# DROduino_v1.net
KiCad netlist of a schematic drawn in EAGLE
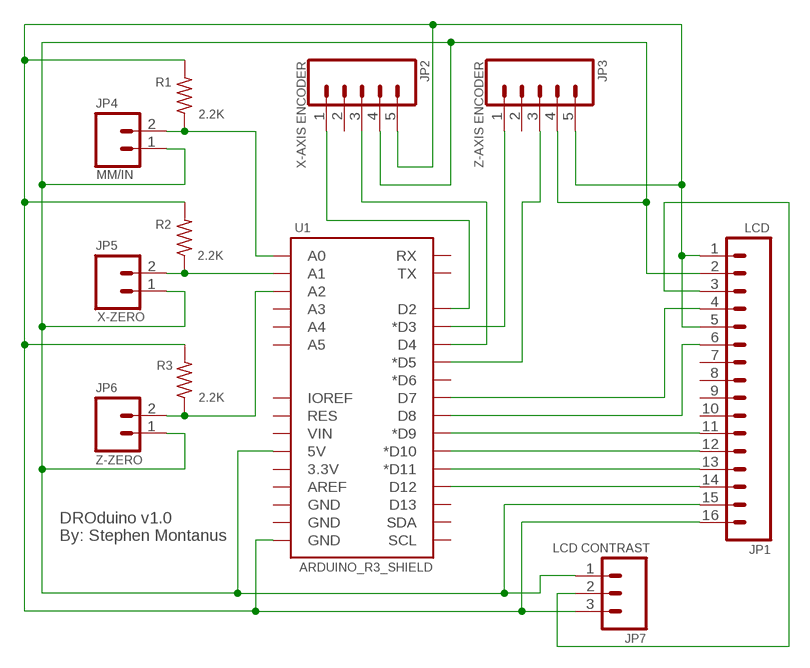
[diagram p0: schematic, sheet 1]

(export (version "E")
  (design (tool "Eeschema 10.0.6"))
  (components
    (comp (ref "JP1")
      (value "LCD")
      (footprint "eagle-import:1X16")
      (libsource (lib "eagle-import") (part "M16PTH"))
    )
    (comp (ref "JP2")
      (value "X-AXIS ENCODER")
      (footprint "eagle-import:1X05")
      (libsource (lib "eagle-import") (part "M05PTH"))
    )
    (comp (ref "JP3")
      (value "Z-AXIS ENCODER")
      (footprint "eagle-import:1X05")
      (libsource (lib "eagle-import") (part "M05PTH"))
    )
    (comp (ref "JP4")
      (value "MM/IN")
      (footprint "eagle-import:1X02")
      (libsource (lib "eagle-import") (part "M02PTH"))
    )
    (comp (ref "JP5")
      (value "X-ZERO")
      (footprint "eagle-import:1X02")
      (libsource (lib "eagle-import") (part "M02PTH"))
    )
    (comp (ref "JP6")
      (value "Z-ZERO")
      (footprint "eagle-import:1X02")
      (libsource (lib "eagle-import") (part "M02PTH"))
    )
    (comp (ref "JP7")
      (value "LCD CONTRAST")
      (footprint "eagle-import:1X03")
      (libsource (lib "eagle-import") (part "M03PTH"))
    )
    (comp (ref "R1")
      (value "2.2K")
      (footprint "eagle-import:0207_10")
      (libsource (lib "eagle-import") (part "R-US_0207/10"))
    )
    (comp (ref "R2")
      (value "2.2K")
      (footprint "eagle-import:0207_10")
      (libsource (lib "eagle-import") (part "R-US_0207/10"))
    )
    (comp (ref "R3")
      (value "2.2K")
      (footprint "eagle-import:0207_10")
      (libsource (lib "eagle-import") (part "R-US_0207/10"))
    )
    (comp (ref "U1")
      (value "ARDUINO_R3_SHIELD")
      (footprint "eagle-import:UNO_R3_SHIELD")
      (libsource (lib "eagle-import") (part "ARDUINO_R3_SHIELD"))
    )
  )
  (nets
    (net (code "1") (name "Net-(JP1-Pad1)") (class "Default")
      (node (ref "JP1") (pin "1") (pinfunction "1_1") (pintype "passive"))
      (node (ref "JP1") (pin "16") (pinfunction "16_16") (pintype "passive"))
      (node (ref "JP1") (pin "5") (pinfunction "5_5") (pintype "passive"))
      (node (ref "JP2") (pin "5") (pinfunction "5_5") (pintype "passive"))
      (node (ref "JP3") (pin "5") (pinfunction "5_5") (pintype "passive"))
      (node (ref "JP7") (pin "3") (pinfunction "3_3") (pintype "passive"))
      (node (ref "R1") (pin "2") (pinfunction "2_2") (pintype "passive"))
      (node (ref "R2") (pin "2") (pinfunction "2_2") (pintype "passive"))
      (node (ref "R3") (pin "2") (pinfunction "2_2") (pintype "passive"))
      (node (ref "U1") (pin "GND@0") (pinfunction "GND_GND@0") (pintype "bidirectional"))
    )
    (net (code "2") (name "Net-(JP1-Pad3)") (class "Default")
      (node (ref "JP1") (pin "3") (pinfunction "3_3") (pintype "passive"))
      (node (ref "JP7") (pin "2") (pinfunction "2_2") (pintype "passive"))
    )
    (net (code "3") (name "Net-(JP1-Pad4)") (class "Default")
      (node (ref "JP1") (pin "4") (pinfunction "4_4") (pintype "passive"))
      (node (ref "U1") (pin "D7") (pinfunction "D7_D7") (pintype "bidirectional"))
    )
    (net (code "4") (name "Net-(JP1-Pad6)") (class "Default")
      (node (ref "JP1") (pin "6") (pinfunction "6_6") (pintype "passive"))
      (node (ref "U1") (pin "D8") (pinfunction "D8_D8") (pintype "bidirectional"))
    )
    (net (code "5") (name "Net-(JP1-Pad14)") (class "Default")
      (node (ref "JP1") (pin "14") (pinfunction "14_14") (pintype "passive"))
      (node (ref "U1") (pin "D12") (pinfunction "D12_D12") (pintype "bidirectional"))
    )
    (net (code "6") (name "Net-(JP1-Pad15)") (class "Default")
      (node (ref "JP1") (pin "15") (pinfunction "15_15") (pintype "passive"))
      (node (ref "JP1") (pin "2") (pinfunction "2_2") (pintype "passive"))
      (node (ref "JP2") (pin "4") (pinfunction "4_4") (pintype "passive"))
      (node (ref "JP3") (pin "4") (pinfunction "4_4") (pintype "passive"))
      (node (ref "JP4") (pin "1") (pinfunction "1_1") (pintype "passive"))
      (node (ref "JP5") (pin "1") (pinfunction "1_1") (pintype "passive"))
      (node (ref "JP6") (pin "1") (pinfunction "1_1") (pintype "passive"))
      (node (ref "JP7") (pin "1") (pinfunction "1_1") (pintype "passive"))
      (node (ref "U1") (pin "5V") (pinfunction "5V_5V") (pintype "bidirectional"))
    )
    (net (code "7") (name "Net-(JP2-Pad1)") (class "Default")
      (node (ref "JP2") (pin "1") (pinfunction "1_1") (pintype "passive"))
      (node (ref "U1") (pin "D2") (pinfunction "D2_D2") (pintype "bidirectional"))
    )
    (net (code "8") (name "Net-(JP2-Pad3)") (class "Default")
      (node (ref "JP2") (pin "3") (pinfunction "3_3") (pintype "passive"))
      (node (ref "U1") (pin "D4") (pinfunction "D4_D4") (pintype "bidirectional"))
    )
    (net (code "9") (name "Net-(JP4-Pad2)") (class "Default")
      (node (ref "JP4") (pin "2") (pinfunction "2_2") (pintype "passive"))
      (node (ref "R1") (pin "1") (pinfunction "1_1") (pintype "passive"))
      (node (ref "U1") (pin "A0") (pinfunction "A0_A0") (pintype "bidirectional"))
    )
    (net (code "10") (name "Net-(JP5-Pad2)") (class "Default")
      (node (ref "JP5") (pin "2") (pinfunction "2_2") (pintype "passive"))
      (node (ref "R2") (pin "1") (pinfunction "1_1") (pintype "passive"))
      (node (ref "U1") (pin "A1") (pinfunction "A1_A1") (pintype "bidirectional"))
    )
    (net (code "11") (name "Net-(JP6-Pad2)") (class "Default")
      (node (ref "JP6") (pin "2") (pinfunction "2_2") (pintype "passive"))
      (node (ref "R3") (pin "1") (pinfunction "1_1") (pintype "passive"))
      (node (ref "U1") (pin "A2") (pinfunction "A2_A2") (pintype "bidirectional"))
    )
    (net (code "12") (name "Net-(U1-*D3)") (class "Default")
      (node (ref "JP3") (pin "1") (pinfunction "1_1") (pintype "passive"))
      (node (ref "U1") (pin "D3") (pinfunction "*D3_D3") (pintype "bidirectional"))
    )
    (net (code "13") (name "Net-(U1-*D5)") (class "Default")
      (node (ref "JP3") (pin "3") (pinfunction "3_3") (pintype "passive"))
      (node (ref "U1") (pin "D5") (pinfunction "*D5_D5") (pintype "bidirectional"))
    )
    (net (code "14") (name "Net-(U1-*D9)") (class "Default")
      (node (ref "JP1") (pin "11") (pinfunction "11_11") (pintype "passive"))
      (node (ref "U1") (pin "D9") (pinfunction "*D9_D9") (pintype "bidirectional"))
    )
    (net (code "15") (name "Net-(U1-*D10)") (class "Default")
      (node (ref "JP1") (pin "12") (pinfunction "12_12") (pintype "passive"))
      (node (ref "U1") (pin "D10") (pinfunction "*D10_D10") (pintype "bidirectional"))
    )
    (net (code "16") (name "Net-(U1-*D11)") (class "Default")
      (node (ref "JP1") (pin "13") (pinfunction "13_13") (pintype "passive"))
      (node (ref "U1") (pin "D11") (pinfunction "*D11_D11") (pintype "bidirectional"))
    )
    (net (code "17") (name "unconnected-(JP1-Pad7)") (class "Default")
      (node (ref "JP1") (pin "7") (pinfunction "7_7") (pintype "passive"))
    )
    (net (code "18") (name "unconnected-(JP1-Pad8)") (class "Default")
      (node (ref "JP1") (pin "8") (pinfunction "8_8") (pintype "passive"))
    )
    (net (code "19") (name "unconnected-(JP1-Pad9)") (class "Default")
      (node (ref "JP1") (pin "9") (pinfunction "9_9") (pintype "passive"))
    )
    (net (code "20") (name "unconnected-(JP1-Pad10)") (class "Default")
      (node (ref "JP1") (pin "10") (pinfunction "10_10") (pintype "passive"))
    )
    (net (code "21") (name "unconnected-(JP2-Pad2)") (class "Default")
      (node (ref "JP2") (pin "2") (pinfunction "2_2") (pintype "passive"))
    )
    (net (code "22") (name "unconnected-(JP3-Pad2)") (class "Default")
      (node (ref "JP3") (pin "2") (pinfunction "2_2") (pintype "passive"))
    )
    (net (code "23") (name "unconnected-(U1-*D6-PadD6)") (class "Default")
      (node (ref "U1") (pin "D6") (pinfunction "*D6_D6") (pintype "bidirectional"))
    )
    (net (code "24") (name "unconnected-(U1-GND-PadGND@1)") (class "Default")
      (node (ref "U1") (pin "GND@1") (pinfunction "GND_GND@1") (pintype "bidirectional"))
    )
    (net (code "25") (name "unconnected-(U1-GND-PadGND@2)") (class "Default")
      (node (ref "U1") (pin "GND@2") (pinfunction "GND_GND@2") (pintype "bidirectional"))
    )
    (net (code "26") (name "unconnected-(U1-Pad3.3V)") (class "Default")
      (node (ref "U1") (pin "3.3V") (pinfunction "3.3V_3.3V") (pintype "bidirectional"))
    )
    (net (code "27") (name "unconnected-(U1-PadA3)") (class "Default")
      (node (ref "U1") (pin "A3") (pinfunction "A3_A3") (pintype "bidirectional"))
    )
    (net (code "28") (name "unconnected-(U1-PadA4)") (class "Default")
      (node (ref "U1") (pin "A4") (pinfunction "A4_A4") (pintype "bidirectional"))
    )
    (net (code "29") (name "unconnected-(U1-PadA5)") (class "Default")
      (node (ref "U1") (pin "A5") (pinfunction "A5_A5") (pintype "bidirectional"))
    )
    (net (code "30") (name "unconnected-(U1-PadAREF)") (class "Default")
      (node (ref "U1") (pin "AREF") (pinfunction "AREF_AREF") (pintype "bidirectional"))
    )
    (net (code "31") (name "unconnected-(U1-PadD13)") (class "Default")
      (node (ref "U1") (pin "D13") (pinfunction "D13_D13") (pintype "bidirectional"))
    )
    (net (code "32") (name "unconnected-(U1-PadIOREF)") (class "Default")
      (node (ref "U1") (pin "IOREF") (pinfunction "IOREF_IOREF") (pintype "bidirectional"))
    )
    (net (code "33") (name "unconnected-(U1-PadRES)") (class "Default")
      (node (ref "U1") (pin "RES") (pinfunction "RES_RES") (pintype "bidirectional"))
    )
    (net (code "34") (name "unconnected-(U1-PadRX)") (class "Default")
      (node (ref "U1") (pin "RX") (pinfunction "RX_RX") (pintype "bidirectional"))
    )
    (net (code "35") (name "unconnected-(U1-PadSCL)") (class "Default")
      (node (ref "U1") (pin "SCL") (pinfunction "SCL_SCL") (pintype "bidirectional"))
    )
    (net (code "36") (name "unconnected-(U1-PadSDA)") (class "Default")
      (node (ref "U1") (pin "SDA") (pinfunction "SDA_SDA") (pintype "bidirectional"))
    )
    (net (code "37") (name "unconnected-(U1-PadTX)") (class "Default")
      (node (ref "U1") (pin "TX") (pinfunction "TX_TX") (pintype "bidirectional"))
    )
    (net (code "38") (name "unconnected-(U1-PadVIN)") (class "Default")
      (node (ref "U1") (pin "VIN") (pinfunction "VIN_VIN") (pintype "bidirectional"))
    )
  )
)
